# main.net
KiCad netlist of a schematic drawn in EAGLE
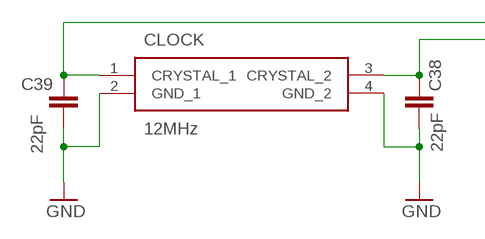
[diagram p0: schematic, sheet 1, part 1 of 3]
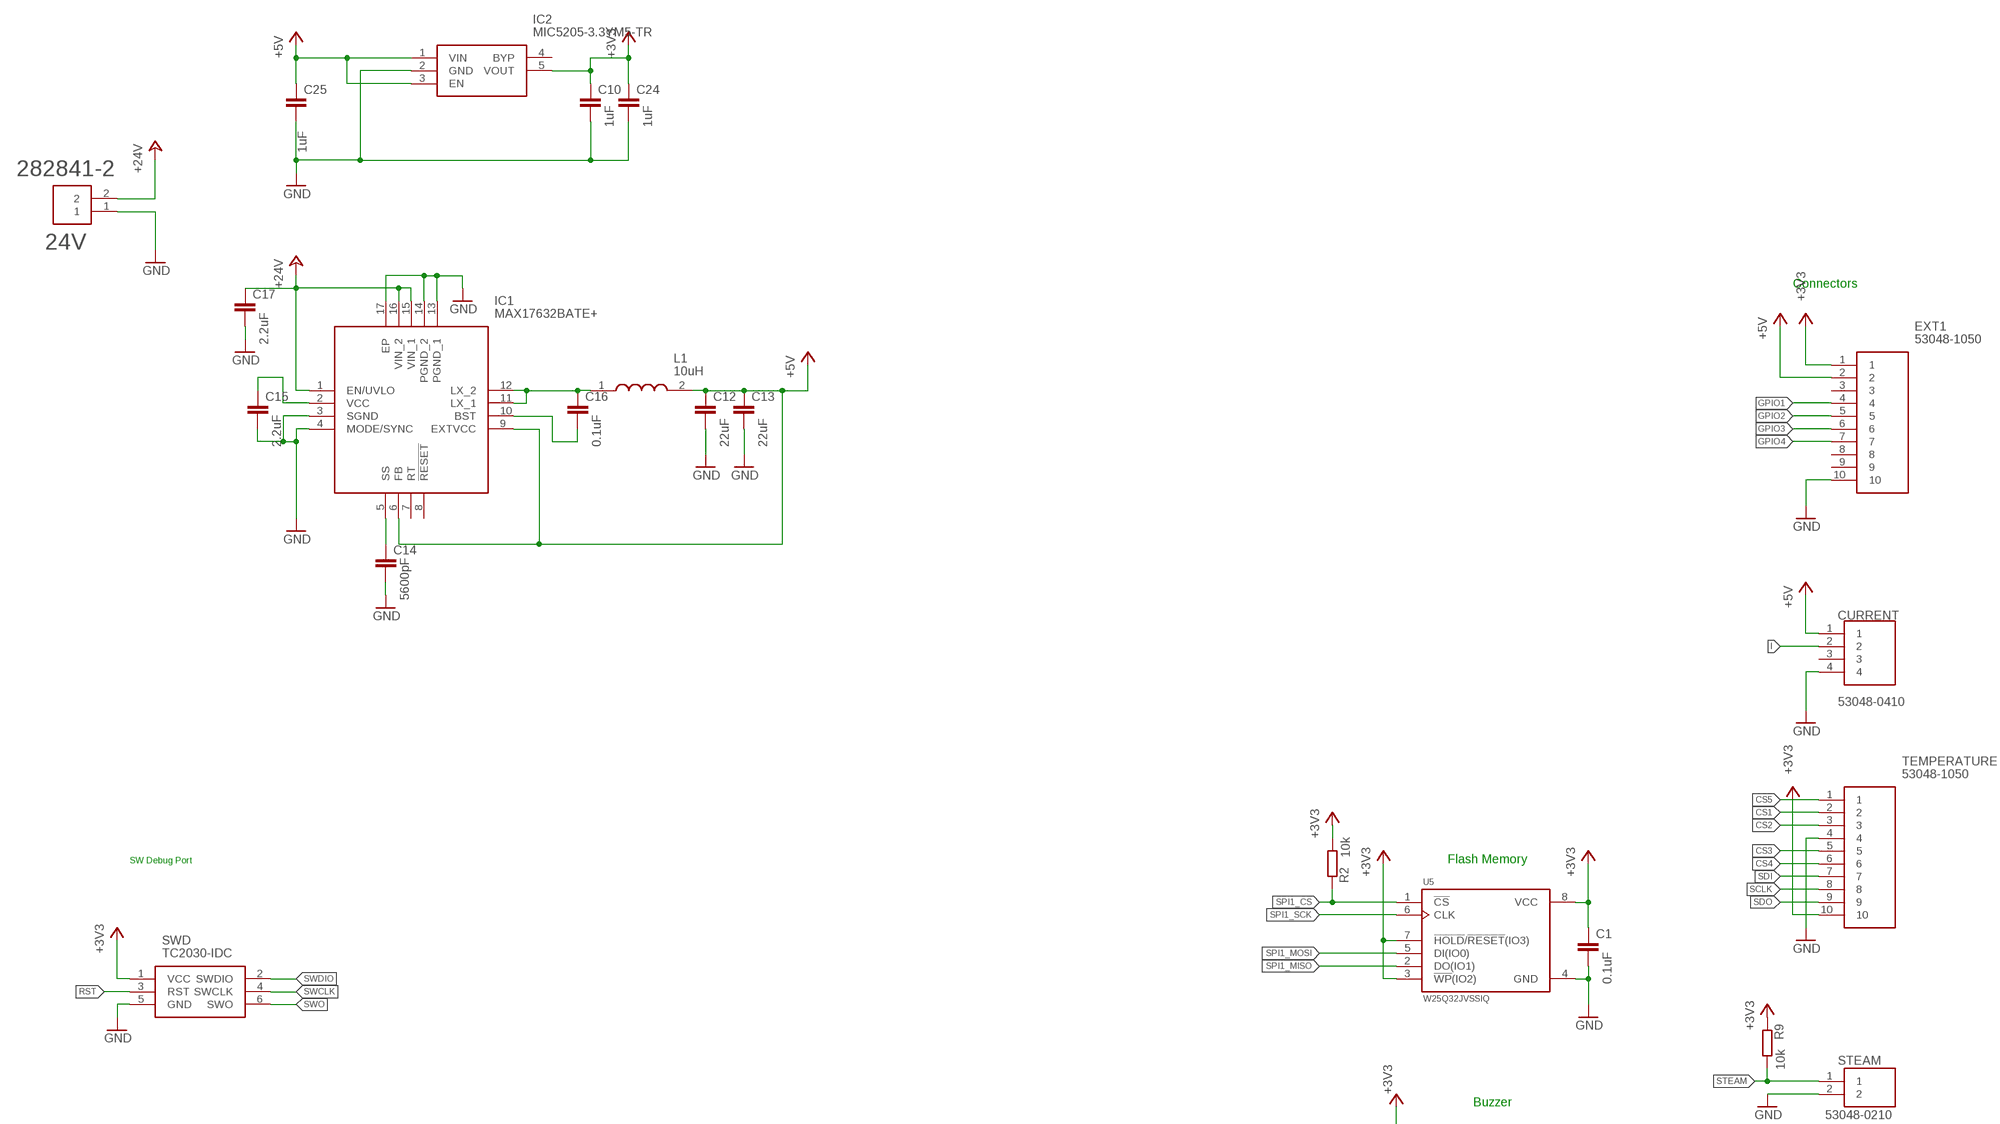
[diagram p1: schematic, sheet 1, part 2 of 3]
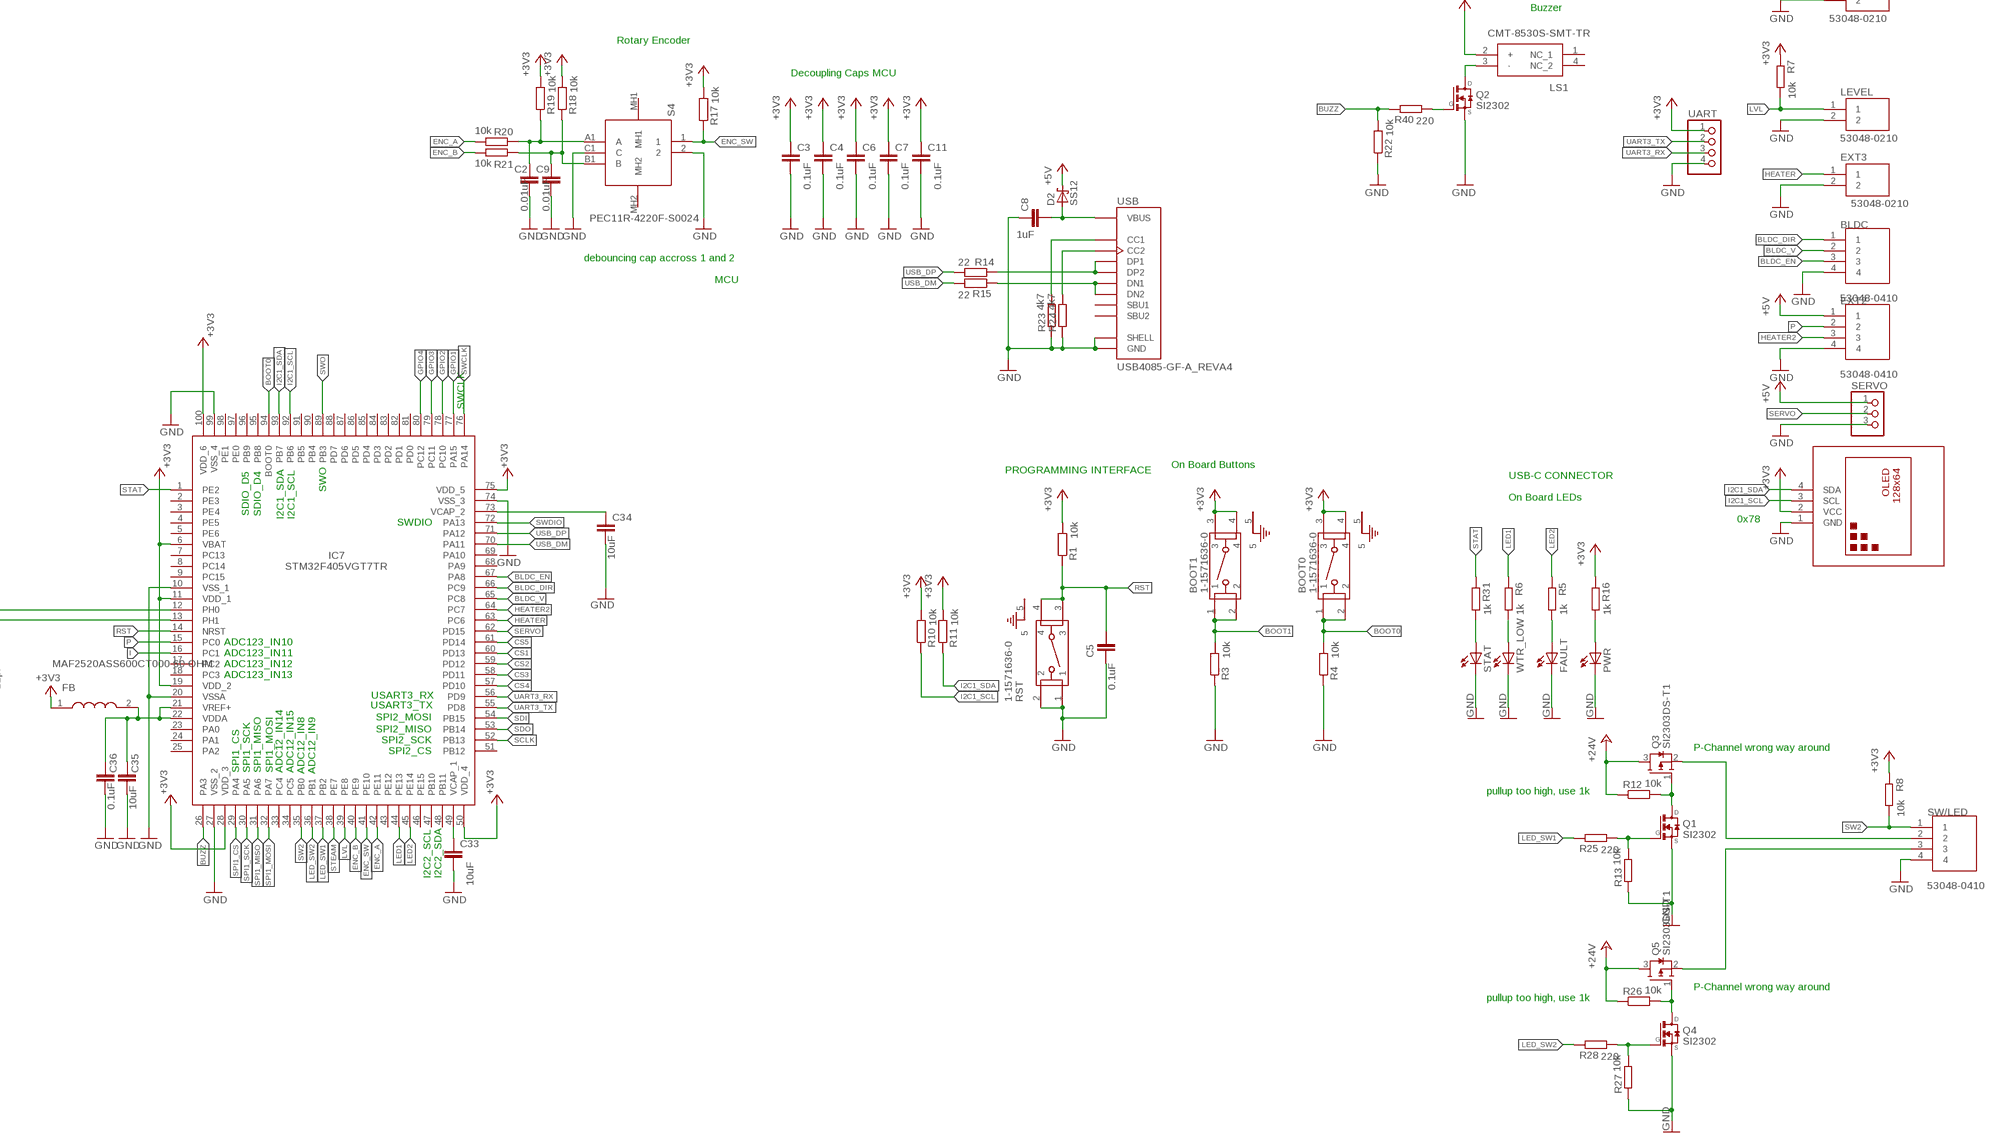
[diagram p2: schematic, sheet 1, part 3 of 3]

(export (version "E")
  (design (tool "Eeschema 10.0.6"))
  (components
    (comp (ref "24V")
      (value "282841-2")
      (footprint "eagle-import:TE_282841-2")
      (fields (field (name "DIGI-KEY_PART_NUMBER") "A98342-ND") (field (name "MF") "TE Connectivity"))
      (libsource (lib "eagle-import") (part "282841-2"))
    )
    (comp (ref "BLDC")
      (value "53048-0410")
      (footprint "eagle-import:530480410")
      (fields (field (name "MOUSER_PART_NUMBER") "538-53048-0410"))
      (libsource (lib "eagle-import") (part "53048-0410"))
    )
    (comp (ref "BOOT0")
      (value "1-1571636-0")
      (footprint "eagle-import:SW5_1571636")
      (fields (field (name "COPYRIGHT") "Copyright (C) 2016 Accelerated Designs. All rights reserved"))
      (libsource (lib "eagle-import") (part "1-1571636-0"))
    )
    (comp (ref "BOOT1")
      (value "1-1571636-0")
      (footprint "eagle-import:SW5_1571636")
      (fields (field (name "COPYRIGHT") "Copyright (C) 2016 Accelerated Designs. All rights reserved"))
      (libsource (lib "eagle-import") (part "1-1571636-0"))
    )
    (comp (ref "C1")
      (value "0.1uF")
      (footprint "eagle-import:C0603K")
      (libsource (lib "eagle-import") (part "C-EUC0603K"))
    )
    (comp (ref "C2")
      (value "0.01uF")
      (footprint "eagle-import:C0603K")
      (libsource (lib "eagle-import") (part "C-EUC0603K"))
    )
    (comp (ref "C3")
      (value "0.1uF")
      (footprint "eagle-import:C0603K")
      (libsource (lib "eagle-import") (part "C-EUC0603K"))
    )
    (comp (ref "C4")
      (value "0.1uF")
      (footprint "eagle-import:C0603K")
      (libsource (lib "eagle-import") (part "C-EUC0603K"))
    )
    (comp (ref "C5")
      (value "0.1uF")
      (footprint "eagle-import:C0603K")
      (libsource (lib "eagle-import") (part "C-EUC0603K"))
    )
    (comp (ref "C6")
      (value "0.1uF")
      (footprint "eagle-import:C0603K")
      (libsource (lib "eagle-import") (part "C-EUC0603K"))
    )
    (comp (ref "C7")
      (value "0.1uF")
      (footprint "eagle-import:C0603K")
      (libsource (lib "eagle-import") (part "C-EUC0603K"))
    )
    (comp (ref "C8")
      (value "1uF")
      (footprint "eagle-import:C0603K")
      (libsource (lib "eagle-import") (part "C-EUC0603K"))
    )
    (comp (ref "C9")
      (value "0.01uF")
      (footprint "eagle-import:C0603K")
      (libsource (lib "eagle-import") (part "C-EUC0603K"))
    )
    (comp (ref "C10")
      (value "1uF")
      (footprint "eagle-import:C0603K")
      (libsource (lib "eagle-import") (part "C-EUC0603K"))
    )
    (comp (ref "C11")
      (value "0.1uF")
      (footprint "eagle-import:C0603K")
      (libsource (lib "eagle-import") (part "C-EUC0603K"))
    )
    (comp (ref "C12")
      (value "22uF")
      (footprint "eagle-import:C0603K")
      (libsource (lib "eagle-import") (part "C-EUC0603K"))
    )
    (comp (ref "C13")
      (value "22uF")
      (footprint "eagle-import:C0603K")
      (libsource (lib "eagle-import") (part "C-EUC0603K"))
    )
    (comp (ref "C14")
      (value "5600pF")
      (footprint "eagle-import:C0603K")
      (libsource (lib "eagle-import") (part "C-EUC0603K"))
    )
    (comp (ref "C15")
      (value "2.2uF")
      (footprint "eagle-import:C0603K")
      (libsource (lib "eagle-import") (part "C-EUC0603K"))
    )
    (comp (ref "C16")
      (value "0.1uF")
      (footprint "eagle-import:C0603K")
      (libsource (lib "eagle-import") (part "C-EUC0603K"))
    )
    (comp (ref "C17")
      (value "2.2uF")
      (footprint "eagle-import:C0603K")
      (libsource (lib "eagle-import") (part "C-EUC0603K"))
    )
    (comp (ref "C24")
      (value "1uF")
      (footprint "eagle-import:C0603K")
      (libsource (lib "eagle-import") (part "C-EUC0603K"))
    )
    (comp (ref "C25")
      (value "1uF")
      (footprint "eagle-import:C0603K")
      (libsource (lib "eagle-import") (part "C-EUC0603K"))
    )
    (comp (ref "C33")
      (value "10uF")
      (footprint "eagle-import:C0603K")
      (libsource (lib "eagle-import") (part "C-EUC0603K"))
    )
    (comp (ref "C34")
      (value "10uF")
      (footprint "eagle-import:C0603K")
      (libsource (lib "eagle-import") (part "C-EUC0603K"))
    )
    (comp (ref "C35")
      (value "10uF")
      (footprint "eagle-import:C0603K")
      (libsource (lib "eagle-import") (part "C-EUC0603K"))
    )
    (comp (ref "C36")
      (value "0.1uF")
      (footprint "eagle-import:C0603K")
      (libsource (lib "eagle-import") (part "C-EUC0603K"))
    )
    (comp (ref "C38")
      (value "22pF")
      (footprint "eagle-import:C0603K")
      (libsource (lib "eagle-import") (part "C-EUC0603K"))
    )
    (comp (ref "C39")
      (value "22pF")
      (footprint "eagle-import:C0603K")
      (libsource (lib "eagle-import") (part "C-EUC0603K"))
    )
    (comp (ref "CLOCK")
      (value "12MHz")
      (footprint "eagle-import:ABM8AIG8000MHZ1ZT")
      (fields
        (field (name "MANUFACTURER_PART_NUMBER") "ABM8AIG-8.000MHZ-1Z-T")
        (field (name "MOUSER_PART_NUMBER") "815-M8AIG-8-1ZT")
      )
      (libsource (lib "eagle-import") (part "ABM8AIG-8.000MHZ-1Z-T"))
    )
    (comp (ref "CURRENT")
      (value "53048-0410")
      (footprint "eagle-import:530480410")
      (fields (field (name "MOUSER_PART_NUMBER") "538-53048-0410"))
      (libsource (lib "eagle-import") (part "53048-0410"))
    )
    (comp (ref "D2")
      (value "SS12")
      (footprint "eagle-import:DO214AC")
      (fields (field (name "MF") "Klein Tools,"))
      (libsource (lib "eagle-import") (part "SS12"))
    )
    (comp (ref "DISPLAY")
      (value "DISPLAY-OLED-128X64-I2C")
      (footprint "eagle-import:DISPLAY-OLED-128X64-I2C")
      (libsource (lib "eagle-import") (part "DISPLAY-OLED-128X64-I2C"))
    )
    (comp (ref "EXT1")
      (value "53048-1050")
      (footprint "eagle-import:SHDRRA10W25P0X125_1X10_1425X55")
      (fields (field (name "MOUSER_PART_NUMBER") "538-53048-1050"))
      (libsource (lib "eagle-import") (part "53048-1050"))
    )
    (comp (ref "EXT2")
      (value "53048-0410")
      (footprint "eagle-import:530480410")
      (fields (field (name "MOUSER_PART_NUMBER") "538-53048-0410"))
      (libsource (lib "eagle-import") (part "53048-0410"))
    )
    (comp (ref "EXT3")
      (value "53048-0210")
      (footprint "eagle-import:SHDRRA2W35P0X125_1X2_425X550X3")
      (fields (field (name "MOUSER_PART_NUMBER") "538-53048-0210"))
      (libsource (lib "eagle-import") (part "53048-0210"))
    )
    (comp (ref "FAULT")
      (value "LEDCHIPLED_0805")
      (footprint "eagle-import:CHIPLED_0805")
      (libsource (lib "eagle-import") (part "LEDCHIPLED_0805"))
    )
    (comp (ref "FB")
      (value "MAF2520ASS600CT000 60 OHM")
      (footprint "eagle-import:INDC2520X120N")
      (fields
        (field (name "MANUFACTURER_PART_NUMBER") "DFE252012P-1R0M=P2")
        (field (name "MOUSER_PART_NUMBER") "81-DFE252012P-1R0MP2")
        (field (name "RS_PART_NUMBER") "1058572P")
      )
      (libsource (lib "eagle-import") (part "DFE252012P-1R0M=P2"))
    )
    (comp (ref "IC1")
      (value "MAX17632BATE+")
      (footprint "eagle-import:QFN50P300X300X80-17N")
      (fields (field (name "MOUSER_PART_NUMBER") "700-MAX17632BATE+"))
      (libsource (lib "eagle-import") (part "MAX17632BATE+"))
    )
    (comp (ref "IC2")
      (value "MIC5205-3.3YM5-TR")
      (footprint "eagle-import:SOT95P280X145-5N")
      (fields (field (name "MOUSER_PART_NUMBER") "998-MIC5205-3.3YM5TR"))
      (libsource (lib "eagle-import") (part "MIC5205-3.3YM5-TR"))
    )
    (comp (ref "IC7")
      (value "STM32F405VGT7TR")
      (footprint "eagle-import:QFP50P1600X1600X160-100N")
      (fields
        (field (name "MOUSER_PART_NUMBER") "511-STM32F405VGT7TR")
        (field (name "RS_PART_NUMBER") "7926025")
      )
      (libsource (lib "eagle-import") (part "STM32F405VGT7TR"))
    )
    (comp (ref "L1")
      (value "10uH")
      (footprint "eagle-import:INDC3225X270N")
      (fields
        (field (name "ARROW_PART_NUMBER") "CBC3225T100KR")
        (field (name "MOUSER_PART_NUMBER") "963-CBC3225T100KR")
      )
      (libsource (lib "eagle-import") (part "CBC3225T100KR"))
    )
    (comp (ref "LEVEL")
      (value "53048-0210")
      (footprint "eagle-import:SHDRRA2W35P0X125_1X2_425X550X3")
      (fields (field (name "MOUSER_PART_NUMBER") "538-53048-0210"))
      (libsource (lib "eagle-import") (part "53048-0210"))
    )
    (comp (ref "LS1")
      (value "CMT-8530S-SMT-TR")
      (footprint "eagle-import:CMT8530SSMTTR")
      (fields (field (name "MOUSER_PART_NUMBER") "490-CMT-8530S-SMT-TR"))
      (libsource (lib "eagle-import") (part "CMT-8530S-SMT-TR"))
    )
    (comp (ref "PWR")
      (value "LEDCHIPLED_0805")
      (footprint "eagle-import:CHIPLED_0805")
      (libsource (lib "eagle-import") (part "LEDCHIPLED_0805"))
    )
    (comp (ref "Q1")
      (value "SI2302")
      (footprint "eagle-import:SOT23")
      (fields (field (name "MF") "Micro Commercial Components _MCC_"))
      (libsource (lib "eagle-import") (part "SI2302"))
    )
    (comp (ref "Q2")
      (value "SI2302")
      (footprint "eagle-import:SOT23")
      (fields (field (name "MF") "Micro Commercial Components _MCC_"))
      (libsource (lib "eagle-import") (part "SI2302"))
    )
    (comp (ref "Q3")
      (value "SI2303DS-T1")
      (footprint "eagle-import:SOT90P248X115-3N")
      (fields (field (name "MOUSER_PART_NUMBER") "781-SI2303DS"))
      (libsource (lib "eagle-import") (part "SI2303DS-T1"))
    )
    (comp (ref "Q4")
      (value "SI2302")
      (footprint "eagle-import:SOT23")
      (fields (field (name "MF") "Micro Commercial Components _MCC_"))
      (libsource (lib "eagle-import") (part "SI2302"))
    )
    (comp (ref "Q5")
      (value "SI2303DS-T1")
      (footprint "eagle-import:SOT90P248X115-3N")
      (fields (field (name "MOUSER_PART_NUMBER") "781-SI2303DS"))
      (libsource (lib "eagle-import") (part "SI2303DS-T1"))
    )
    (comp (ref "R1")
      (value "10k")
      (footprint "eagle-import:R0603")
      (libsource (lib "eagle-import") (part "R-EU_R0603"))
    )
    (comp (ref "R2")
      (value "10k")
      (footprint "eagle-import:R0603")
      (libsource (lib "eagle-import") (part "R-EU_R0603"))
    )
    (comp (ref "R3")
      (value "10k")
      (footprint "eagle-import:R0603")
      (libsource (lib "eagle-import") (part "R-EU_R0603"))
    )
    (comp (ref "R4")
      (value "10k")
      (footprint "eagle-import:R0603")
      (libsource (lib "eagle-import") (part "R-EU_R0603"))
    )
    (comp (ref "R5")
      (value "1k")
      (footprint "eagle-import:R0603")
      (libsource (lib "eagle-import") (part "R-EU_R0603"))
    )
    (comp (ref "R6")
      (value "1k")
      (footprint "eagle-import:R0603")
      (libsource (lib "eagle-import") (part "R-EU_R0603"))
    )
    (comp (ref "R7")
      (value "10k")
      (footprint "eagle-import:R0603")
      (libsource (lib "eagle-import") (part "R-EU_R0603"))
    )
    (comp (ref "R8")
      (value "10k")
      (footprint "eagle-import:R0603")
      (libsource (lib "eagle-import") (part "R-EU_R0603"))
    )
    (comp (ref "R9")
      (value "10k")
      (footprint "eagle-import:R0603")
      (libsource (lib "eagle-import") (part "R-EU_R0603"))
    )
    (comp (ref "R10")
      (value "10k")
      (footprint "eagle-import:R0603")
      (libsource (lib "eagle-import") (part "R-EU_R0603"))
    )
    (comp (ref "R11")
      (value "10k")
      (footprint "eagle-import:R0603")
      (libsource (lib "eagle-import") (part "R-EU_R0603"))
    )
    (comp (ref "R12")
      (value "10k")
      (footprint "eagle-import:R0603")
      (libsource (lib "eagle-import") (part "R-EU_R0603"))
    )
    (comp (ref "R13")
      (value "10k")
      (footprint "eagle-import:R0603")
      (libsource (lib "eagle-import") (part "R-EU_R0603"))
    )
    (comp (ref "R14")
      (value "22")
      (footprint "eagle-import:R0603")
      (libsource (lib "eagle-import") (part "R-EU_R0603"))
    )
    (comp (ref "R15")
      (value "22")
      (footprint "eagle-import:R0603")
      (libsource (lib "eagle-import") (part "R-EU_R0603"))
    )
    (comp (ref "R16")
      (value "1k")
      (footprint "eagle-import:R0603")
      (libsource (lib "eagle-import") (part "R-EU_R0603"))
    )
    (comp (ref "R17")
      (value "10k")
      (footprint "eagle-import:R0603")
      (libsource (lib "eagle-import") (part "R-EU_R0603"))
    )
    (comp (ref "R18")
      (value "10k")
      (footprint "eagle-import:R0603")
      (libsource (lib "eagle-import") (part "R-EU_R0603"))
    )
    (comp (ref "R19")
      (value "10k")
      (footprint "eagle-import:R0603")
      (libsource (lib "eagle-import") (part "R-EU_R0603"))
    )
    (comp (ref "R20")
      (value "10k")
      (footprint "eagle-import:R0603")
      (libsource (lib "eagle-import") (part "R-EU_R0603"))
    )
    (comp (ref "R21")
      (value "10k")
      (footprint "eagle-import:R0603")
      (libsource (lib "eagle-import") (part "R-EU_R0603"))
    )
    (comp (ref "R22")
      (value "10k")
      (footprint "eagle-import:R0603")
      (libsource (lib "eagle-import") (part "R-EU_R0603"))
    )
    (comp (ref "R23")
      (value "4k7")
      (footprint "eagle-import:R0603")
      (libsource (lib "eagle-import") (part "R-EU_R0603"))
    )
    (comp (ref "R24")
      (value "4k7")
      (footprint "eagle-import:R0603")
      (libsource (lib "eagle-import") (part "R-EU_R0603"))
    )
    (comp (ref "R25")
      (value "220")
      (footprint "eagle-import:R0603")
      (libsource (lib "eagle-import") (part "R-EU_R0603"))
    )
    (comp (ref "R26")
      (value "10k")
      (footprint "eagle-import:R0603")
      (libsource (lib "eagle-import") (part "R-EU_R0603"))
    )
    (comp (ref "R27")
      (value "10k")
      (footprint "eagle-import:R0603")
      (libsource (lib "eagle-import") (part "R-EU_R0603"))
    )
    (comp (ref "R28")
      (value "220")
      (footprint "eagle-import:R0603")
      (libsource (lib "eagle-import") (part "R-EU_R0603"))
    )
    (comp (ref "R31")
      (value "1k")
      (footprint "eagle-import:R0603")
      (libsource (lib "eagle-import") (part "R-EU_R0603"))
    )
    (comp (ref "R40")
      (value "220")
      (footprint "eagle-import:R0603")
      (libsource (lib "eagle-import") (part "R-EU_R0603"))
    )
    (comp (ref "RST")
      (value "1-1571636-0")
      (footprint "eagle-import:SW5_1571636")
      (fields (field (name "COPYRIGHT") "Copyright (C) 2016 Accelerated Designs. All rights reserved"))
      (libsource (lib "eagle-import") (part "1-1571636-0"))
    )
    (comp (ref "S4")
      (value "PEC11R-4220F-S0024")
      (footprint "eagle-import:PEC11R4220FS0024")
      (fields (field (name "MOUSER_PART_NUMBER") "652-PEC11R-4220F-S24"))
      (libsource (lib "eagle-import") (part "PEC11R-4220F-S0024"))
    )
    (comp (ref "SERVO")
      (value "PINHD-1X3/90")
      (footprint "eagle-import:1X03_90")
      (libsource (lib "eagle-import") (part "PINHD-1X3/90"))
    )
    (comp (ref "STAT")
      (value "LEDCHIPLED_0805")
      (footprint "eagle-import:CHIPLED_0805")
      (libsource (lib "eagle-import") (part "LEDCHIPLED_0805"))
    )
    (comp (ref "STEAM")
      (value "53048-0210")
      (footprint "eagle-import:SHDRRA2W35P0X125_1X2_425X550X3")
      (fields (field (name "MOUSER_PART_NUMBER") "538-53048-0210"))
      (libsource (lib "eagle-import") (part "53048-0210"))
    )
    (comp (ref "SW/LED")
      (value "53048-0410")
      (footprint "eagle-import:530480410")
      (fields (field (name "MOUSER_PART_NUMBER") "538-53048-0410"))
      (libsource (lib "eagle-import") (part "53048-0410"))
    )
    (comp (ref "SWD")
      (value "TC2030-IDC")
      (footprint "eagle-import:TC2030IDC")
      (libsource (lib "eagle-import") (part "TC2030-IDC"))
    )
    (comp (ref "TEMPERATURE")
      (value "53048-1050")
      (footprint "eagle-import:SHDRRA10W25P0X125_1X10_1425X55")
      (fields (field (name "MOUSER_PART_NUMBER") "538-53048-1050"))
      (libsource (lib "eagle-import") (part "53048-1050"))
    )
    (comp (ref "U5")
      (value "W25Q32JVSSIQ")
      (footprint "eagle-import:SOIC127P790X216-8N")
      (fields (field (name "MF") "Winbond"))
      (libsource (lib "eagle-import") (part "W25Q32JVSSIQ"))
    )
    (comp (ref "UART")
      (value "PINHD-1X4")
      (footprint "eagle-import:1X04")
      (libsource (lib "eagle-import") (part "PINHD-1X4"))
    )
    (comp (ref "USB")
      (value "USB4085-GF-A_REVA4")
      (footprint "eagle-import:GCT_USB4085-GF-A_REVA4")
      (fields (field (name "MF") "Global Connector Technology") (field (name "MP") "USB4085-GF-A"))
      (libsource (lib "eagle-import") (part "USB4085-GF-A_REVA4"))
    )
    (comp (ref "WTR_LOW")
      (value "LEDCHIPLED_0805")
      (footprint "eagle-import:CHIPLED_0805")
      (libsource (lib "eagle-import") (part "LEDCHIPLED_0805"))
    )
  )
  (nets
    (net (code "1") (name "+3V3") (class "Default")
      (node (ref "BOOT0") (pin "3") (pinfunction "3_3") (pintype "passive"))
      (node (ref "BOOT0") (pin "4") (pinfunction "4_4") (pintype "passive"))
      (node (ref "BOOT1") (pin "3") (pinfunction "3_3") (pintype "passive"))
      (node (ref "BOOT1") (pin "4") (pinfunction "4_4") (pintype "passive"))
      (node (ref "C1") (pin "1") (pinfunction "1_1") (pintype "passive"))
      (node (ref "C10") (pin "1") (pinfunction "1_1") (pintype "passive"))
      (node (ref "C11") (pin "1") (pinfunction "1_1") (pintype "passive"))
      (node (ref "C24") (pin "1") (pinfunction "1_1") (pintype "passive"))
      (node (ref "C3") (pin "1") (pinfunction "1_1") (pintype "passive"))
      (node (ref "C4") (pin "1") (pinfunction "1_1") (pintype "passive"))
      (node (ref "C6") (pin "1") (pinfunction "1_1") (pintype "passive"))
      (node (ref "C7") (pin "1") (pinfunction "1_1") (pintype "passive"))
      (node (ref "DISPLAY") (pin "2") (pinfunction "VCC_2") (pintype "power_in"))
      (node (ref "EXT1") (pin "1") (pinfunction "1_1") (pintype "bidirectional"))
      (node (ref "FB") (pin "1") (pinfunction "1_1") (pintype "bidirectional"))
      (node (ref "IC2") (pin "5") (pinfunction "VOUT_5") (pintype "power_in"))
      (node (ref "IC7") (pin "100") (pinfunction "VDD_6_100") (pintype "power_in"))
      (node (ref "IC7") (pin "11") (pinfunction "VDD_1_11") (pintype "power_in"))
      (node (ref "IC7") (pin "19") (pinfunction "VDD_2_19") (pintype "power_in"))
      (node (ref "IC7") (pin "28") (pinfunction "VDD_3_28") (pintype "power_in"))
      (node (ref "IC7") (pin "50") (pinfunction "VDD_4_50") (pintype "power_in"))
      (node (ref "IC7") (pin "6") (pinfunction "VBAT_6") (pintype "bidirectional"))
      (node (ref "IC7") (pin "75") (pinfunction "VDD_5_75") (pintype "power_in"))
      (node (ref "LS1") (pin "2") (pinfunction "+_2") (pintype "bidirectional"))
      (node (ref "R1") (pin "2") (pinfunction "2_2") (pintype "passive"))
      (node (ref "R10") (pin "2") (pinfunction "2_2") (pintype "passive"))
      (node (ref "R11") (pin "2") (pinfunction "2_2") (pintype "passive"))
      (node (ref "R16") (pin "1") (pinfunction "1_1") (pintype "passive"))
      (node (ref "R17") (pin "2") (pinfunction "2_2") (pintype "passive"))
      (node (ref "R18") (pin "2") (pinfunction "2_2") (pintype "passive"))
      (node (ref "R19") (pin "2") (pinfunction "2_2") (pintype "passive"))
      (node (ref "R2") (pin "2") (pinfunction "2_2") (pintype "passive"))
      (node (ref "R7") (pin "1") (pinfunction "1_1") (pintype "passive"))
      (node (ref "R8") (pin "1") (pinfunction "1_1") (pintype "passive"))
      (node (ref "R9") (pin "1") (pinfunction "1_1") (pintype "passive"))
      (node (ref "SWD") (pin "1") (pinfunction "VCC_1") (pintype "bidirectional"))
      (node (ref "TEMPERATURE") (pin "10") (pinfunction "10_10") (pintype "bidirectional"))
      (node (ref "U5") (pin "3") (pinfunction "~{WP}(IO2)_3") (pintype "bidirectional"))
      (node (ref "U5") (pin "7") (pinfunction "~{HOLD}/~{RESET}(IO3)_7") (pintype "bidirectional"))
      (node (ref "U5") (pin "8") (pinfunction "VCC_8") (pintype "power_in"))
      (node (ref "UART") (pin "1") (pinfunction "1_1") (pintype "passive"))
    )
    (net (code "2") (name "+5V") (class "Default")
      (node (ref "C12") (pin "1") (pinfunction "1_1") (pintype "passive"))
      (node (ref "C13") (pin "1") (pinfunction "1_1") (pintype "passive"))
      (node (ref "C25") (pin "1") (pinfunction "1_1") (pintype "passive"))
      (node (ref "CURRENT") (pin "1") (pinfunction "1_1") (pintype "bidirectional"))
      (node (ref "D2") (pin "C") (pinfunction "C_C") (pintype "passive"))
      (node (ref "EXT1") (pin "2") (pinfunction "2_2") (pintype "bidirectional"))
      (node (ref "EXT2") (pin "1") (pinfunction "1_1") (pintype "bidirectional"))
      (node (ref "IC1") (pin "6") (pinfunction "FB_6") (pintype "bidirectional"))
      (node (ref "IC1") (pin "9") (pinfunction "EXTVCC_9") (pintype "bidirectional"))
      (node (ref "IC2") (pin "1") (pinfunction "VIN_1") (pintype "power_in"))
      (node (ref "IC2") (pin "3") (pinfunction "EN_3") (pintype "input"))
      (node (ref "L1") (pin "2") (pinfunction "2_2") (pintype "bidirectional"))
      (node (ref "SERVO") (pin "1") (pinfunction "1_1") (pintype "passive"))
    )
    (net (code "3") (name "+24V") (class "Default")
      (node (ref "24V") (pin "2") (pinfunction "2_2") (pintype "passive"))
      (node (ref "C17") (pin "1") (pinfunction "1_1") (pintype "passive"))
      (node (ref "IC1") (pin "1") (pinfunction "EN/UVLO_1") (pintype "bidirectional"))
      (node (ref "IC1") (pin "15") (pinfunction "VIN_1_15") (pintype "bidirectional"))
      (node (ref "IC1") (pin "16") (pinfunction "VIN_2_16") (pintype "bidirectional"))
      (node (ref "Q3") (pin "3") (pinfunction "D_3") (pintype "bidirectional"))
      (node (ref "Q5") (pin "3") (pinfunction "D_3") (pintype "bidirectional"))
      (node (ref "R12") (pin "1") (pinfunction "1_1") (pintype "passive"))
      (node (ref "R26") (pin "1") (pinfunction "1_1") (pintype "passive"))
    )
    (net (code "4") (name "BLDC_DIR") (class "Default")
      (node (ref "BLDC") (pin "1") (pinfunction "1_1") (pintype "bidirectional"))
      (node (ref "IC7") (pin "66") (pinfunction "PC9_66") (pintype "bidirectional"))
    )
    (net (code "5") (name "BLDC_EN") (class "Default")
      (node (ref "BLDC") (pin "3") (pinfunction "3_3") (pintype "bidirectional"))
      (node (ref "IC7") (pin "67") (pinfunction "PA8_67") (pintype "bidirectional"))
    )
    (net (code "6") (name "BLDC_V") (class "Default")
      (node (ref "BLDC") (pin "2") (pinfunction "2_2") (pintype "bidirectional"))
      (node (ref "IC7") (pin "65") (pinfunction "PC8_65") (pintype "bidirectional"))
    )
    (net (code "7") (name "BOOT0") (class "Default")
      (node (ref "BOOT0") (pin "1") (pinfunction "1_1") (pintype "passive"))
      (node (ref "BOOT0") (pin "2") (pinfunction "2_2") (pintype "passive"))
      (node (ref "IC7") (pin "94") (pinfunction "BOOT0_94") (pintype "bidirectional"))
      (node (ref "R4") (pin "2") (pinfunction "2_2") (pintype "passive"))
    )
    (net (code "8") (name "BOOT1") (class "Default")
      (node (ref "BOOT1") (pin "1") (pinfunction "1_1") (pintype "passive"))
      (node (ref "BOOT1") (pin "2") (pinfunction "2_2") (pintype "passive"))
      (node (ref "R3") (pin "2") (pinfunction "2_2") (pintype "passive"))
    )
    (net (code "9") (name "BUZZ") (class "Default")
      (node (ref "IC7") (pin "26") (pinfunction "PA3_26") (pintype "bidirectional"))
      (node (ref "R22") (pin "2") (pinfunction "2_2") (pintype "passive"))
      (node (ref "R40") (pin "1") (pinfunction "1_1") (pintype "passive"))
    )
    (net (code "10") (name "CS1") (class "Default")
      (node (ref "IC7") (pin "60") (pinfunction "PD13_60") (pintype "bidirectional"))
      (node (ref "TEMPERATURE") (pin "2") (pinfunction "2_2") (pintype "bidirectional"))
    )
    (net (code "11") (name "CS2") (class "Default")
      (node (ref "IC7") (pin "59") (pinfunction "PD12_59") (pintype "bidirectional"))
      (node (ref "TEMPERATURE") (pin "3") (pinfunction "3_3") (pintype "bidirectional"))
    )
    (net (code "12") (name "CS3") (class "Default")
      (node (ref "IC7") (pin "58") (pinfunction "PD11_58") (pintype "bidirectional"))
      (node (ref "TEMPERATURE") (pin "5") (pinfunction "5_5") (pintype "bidirectional"))
    )
    (net (code "13") (name "CS4") (class "Default")
      (node (ref "IC7") (pin "57") (pinfunction "PD10_57") (pintype "bidirectional"))
      (node (ref "TEMPERATURE") (pin "6") (pinfunction "6_6") (pintype "bidirectional"))
    )
    (net (code "14") (name "CS5") (class "Default")
      (node (ref "IC7") (pin "61") (pinfunction "PD14_61") (pintype "bidirectional"))
      (node (ref "TEMPERATURE") (pin "1") (pinfunction "1_1") (pintype "bidirectional"))
    )
    (net (code "15") (name "ENC_A") (class "Default")
      (node (ref "IC7") (pin "42") (pinfunction "PE11_42") (pintype "bidirectional"))
      (node (ref "R20") (pin "2") (pinfunction "2_2") (pintype "passive"))
    )
    (net (code "16") (name "ENC_B") (class "Default")
      (node (ref "IC7") (pin "40") (pinfunction "PE9_40") (pintype "bidirectional"))
      (node (ref "R21") (pin "2") (pinfunction "2_2") (pintype "passive"))
    )
    (net (code "17") (name "ENC_SW") (class "Default")
      (node (ref "IC7") (pin "41") (pinfunction "PE10_41") (pintype "bidirectional"))
      (node (ref "R17") (pin "1") (pinfunction "1_1") (pintype "passive"))
      (node (ref "S4") (pin "1") (pinfunction "1_1") (pintype "bidirectional"))
    )
    (net (code "18") (name "GND") (class "Default")
      (node (ref "24V") (pin "1") (pinfunction "1_1") (pintype "passive"))
      (node (ref "BLDC") (pin "4") (pinfunction "4_4") (pintype "bidirectional"))
      (node (ref "C1") (pin "2") (pinfunction "2_2") (pintype "passive"))
      (node (ref "C10") (pin "2") (pinfunction "2_2") (pintype "passive"))
      (node (ref "C11") (pin "2") (pinfunction "2_2") (pintype "passive"))
      (node (ref "C12") (pin "2") (pinfunction "2_2") (pintype "passive"))
      (node (ref "C13") (pin "2") (pinfunction "2_2") (pintype "passive"))
      (node (ref "C14") (pin "2") (pinfunction "2_2") (pintype "passive"))
      (node (ref "C15") (pin "2") (pinfunction "2_2") (pintype "passive"))
      (node (ref "C17") (pin "2") (pinfunction "2_2") (pintype "passive"))
      (node (ref "C2") (pin "2") (pinfunction "2_2") (pintype "passive"))
      (node (ref "C24") (pin "2") (pinfunction "2_2") (pintype "passive"))
      (node (ref "C25") (pin "2") (pinfunction "2_2") (pintype "passive"))
      (node (ref "C3") (pin "2") (pinfunction "2_2") (pintype "passive"))
      (node (ref "C33") (pin "2") (pinfunction "2_2") (pintype "passive"))
      (node (ref "C34") (pin "2") (pinfunction "2_2") (pintype "passive"))
      (node (ref "C35") (pin "2") (pinfunction "2_2") (pintype "passive"))
      (node (ref "C36") (pin "2") (pinfunction "2_2") (pintype "passive"))
      (node (ref "C38") (pin "2") (pinfunction "2_2") (pintype "passive"))
      (node (ref "C39") (pin "2") (pinfunction "2_2") (pintype "passive"))
      (node (ref "C4") (pin "2") (pinfunction "2_2") (pintype "passive"))
      (node (ref "C5") (pin "2") (pinfunction "2_2") (pintype "passive"))
      (node (ref "C6") (pin "2") (pinfunction "2_2") (pintype "passive"))
      (node (ref "C7") (pin "2") (pinfunction "2_2") (pintype "passive"))
      (node (ref "C8") (pin "1") (pinfunction "1_1") (pintype "passive"))
      (node (ref "C9") (pin "2") (pinfunction "2_2") (pintype "passive"))
      (node (ref "CLOCK") (pin "2") (pinfunction "GND_1_2") (pintype "bidirectional"))
      (node (ref "CLOCK") (pin "4") (pinfunction "GND_2_4") (pintype "bidirectional"))
      (node (ref "CURRENT") (pin "4") (pinfunction "4_4") (pintype "bidirectional"))
      (node (ref "DISPLAY") (pin "1") (pinfunction "GND_1") (pintype "power_in"))
      (node (ref "EXT1") (pin "10") (pinfunction "10_10") (pintype "bidirectional"))
      (node (ref "EXT2") (pin "4") (pinfunction "4_4") (pintype "bidirectional"))
      (node (ref "EXT3") (pin "2") (pinfunction "2_2") (pintype "bidirectional"))
      (node (ref "FAULT") (pin "C") (pinfunction "C_C") (pintype "passive"))
      (node (ref "IC1") (pin "13") (pinfunction "PGND_1_13") (pintype "bidirectional"))
      (node (ref "IC1") (pin "14") (pinfunction "PGND_2_14") (pintype "bidirectional"))
      (node (ref "IC1") (pin "17") (pinfunction "EP_17") (pintype "bidirectional"))
      (node (ref "IC1") (pin "3") (pinfunction "SGND_3") (pintype "bidirectional"))
      (node (ref "IC1") (pin "4") (pinfunction "MODE/SYNC_4") (pintype "bidirectional"))
      (node (ref "IC2") (pin "2") (pinfunction "GND_2") (pintype "power_in"))
      (node (ref "IC7") (pin "10") (pinfunction "VSS_1_10") (pintype "power_in"))
      (node (ref "IC7") (pin "20") (pinfunction "VSSA_20") (pintype "power_in"))
      (node (ref "IC7") (pin "27") (pinfunction "VSS_2_27") (pintype "power_in"))
      (node (ref "IC7") (pin "74") (pinfunction "VSS_3_74") (pintype "power_in"))
      (node (ref "IC7") (pin "99") (pinfunction "VSS_4_99") (pintype "power_in"))
      (node (ref "LEVEL") (pin "2") (pinfunction "2_2") (pintype "bidirectional"))
      (node (ref "PWR") (pin "C") (pinfunction "C_C") (pintype "passive"))
      (node (ref "Q1") (pin "2") (pinfunction "S_2") (pintype "passive"))
      (node (ref "Q2") (pin "2") (pinfunction "S_2") (pintype "passive"))
      (node (ref "Q4") (pin "2") (pinfunction "S_2") (pintype "passive"))
      (node (ref "R13") (pin "1") (pinfunction "1_1") (pintype "passive"))
      (node (ref "R22") (pin "1") (pinfunction "1_1") (pintype "passive"))
      (node (ref "R23") (pin "1") (pinfunction "1_1") (pintype "passive"))
      (node (ref "R24") (pin "1") (pinfunction "1_1") (pintype "passive"))
      (node (ref "R27") (pin "1") (pinfunction "1_1") (pintype "passive"))
      (node (ref "R3") (pin "1") (pinfunction "1_1") (pintype "passive"))
      (node (ref "R4") (pin "1") (pinfunction "1_1") (pintype "passive"))
      (node (ref "RST") (pin "1") (pinfunction "1_1") (pintype "passive"))
      (node (ref "RST") (pin "2") (pinfunction "2_2") (pintype "passive"))
      (node (ref "S4") (pin "2") (pinfunction "2_2") (pintype "bidirectional"))
      (node (ref "S4") (pin "C1") (pinfunction "C_C1") (pintype "bidirectional"))
      (node (ref "SERVO") (pin "3") (pinfunction "3_3") (pintype "passive"))
      (node (ref "STAT") (pin "C") (pinfunction "C_C") (pintype "passive"))
      (node (ref "STEAM") (pin "2") (pinfunction "2_2") (pintype "bidirectional"))
      (node (ref "SW/LED") (pin "4") (pinfunction "4_4") (pintype "bidirectional"))
      (node (ref "SWD") (pin "5") (pinfunction "GND_5") (pintype "bidirectional"))
      (node (ref "TEMPERATURE") (pin "4") (pinfunction "4_4") (pintype "bidirectional"))
      (node (ref "U5") (pin "4") (pinfunction "GND_4") (pintype "power_in"))
      (node (ref "UART") (pin "4") (pinfunction "4_4") (pintype "passive"))
      (node (ref "USB") (pin "A1") (pinfunction "GND_A1") (pintype "passive"))
      (node (ref "USB") (pin "A12") (pinfunction "GND_A12") (pintype "passive"))
      (node (ref "USB") (pin "B1") (pinfunction "GND_B1") (pintype "passive"))
      (node (ref "USB") (pin "B12") (pinfunction "GND_B12") (pintype "passive"))
      (node (ref "USB") (pin "P1") (pinfunction "SHELL_P1") (pintype "passive"))
      (node (ref "USB") (pin "P2") (pinfunction "SHELL_P2") (pintype "passive"))
      (node (ref "USB") (pin "P3") (pinfunction "SHELL_P3") (pintype "passive"))
      (node (ref "USB") (pin "P4") (pinfunction "SHELL_P4") (pintype "passive"))
      (node (ref "WTR_LOW") (pin "C") (pinfunction "C_C") (pintype "passive"))
    )
    (net (code "19") (name "GPIO1") (class "Default")
      (node (ref "EXT1") (pin "4") (pinfunction "4_4") (pintype "bidirectional"))
      (node (ref "IC7") (pin "77") (pinfunction "PA15_77") (pintype "bidirectional"))
    )
    (net (code "20") (name "GPIO2") (class "Default")
      (node (ref "EXT1") (pin "5") (pinfunction "5_5") (pintype "bidirectional"))
      (node (ref "IC7") (pin "78") (pinfunction "PC10_78") (pintype "bidirectional"))
    )
    (net (code "21") (name "GPIO3") (class "Default")
      (node (ref "EXT1") (pin "6") (pinfunction "6_6") (pintype "bidirectional"))
      (node (ref "IC7") (pin "79") (pinfunction "PC11_79") (pintype "bidirectional"))
    )
    (net (code "22") (name "GPIO4") (class "Default")
      (node (ref "EXT1") (pin "7") (pinfunction "7_7") (pintype "bidirectional"))
      (node (ref "IC7") (pin "80") (pinfunction "PC12_80") (pintype "bidirectional"))
    )
    (net (code "23") (name "HEATER") (class "Default")
      (node (ref "EXT3") (pin "1") (pinfunction "1_1") (pintype "bidirectional"))
      (node (ref "IC7") (pin "63") (pinfunction "PC6_63") (pintype "bidirectional"))
    )
    (net (code "24") (name "HEATER2") (class "Default")
      (node (ref "EXT2") (pin "3") (pinfunction "3_3") (pintype "bidirectional"))
      (node (ref "IC7") (pin "64") (pinfunction "PC7_64") (pintype "bidirectional"))
    )
    (net (code "25") (name "I") (class "Default")
      (node (ref "CURRENT") (pin "2") (pinfunction "2_2") (pintype "bidirectional"))
      (node (ref "IC7") (pin "16") (pinfunction "PC1_16") (pintype "bidirectional"))
    )
    (net (code "26") (name "I2C1_SCL") (class "Default")
      (node (ref "DISPLAY") (pin "3") (pinfunction "SCL_3") (pintype "bidirectional"))
      (node (ref "IC7") (pin "92") (pinfunction "PB6_92") (pintype "bidirectional"))
      (node (ref "R10") (pin "1") (pinfunction "1_1") (pintype "passive"))
    )
    (net (code "27") (name "I2C1_SDA") (class "Default")
      (node (ref "DISPLAY") (pin "4") (pinfunction "SDA_4") (pintype "bidirectional"))
      (node (ref "IC7") (pin "93") (pinfunction "PB7_93") (pintype "bidirectional"))
      (node (ref "R11") (pin "1") (pinfunction "1_1") (pintype "passive"))
    )
    (net (code "28") (name "LED1") (class "Default")
      (node (ref "IC7") (pin "44") (pinfunction "PE13_44") (pintype "bidirectional"))
      (node (ref "R6") (pin "1") (pinfunction "1_1") (pintype "passive"))
    )
    (net (code "29") (name "LED2") (class "Default")
      (node (ref "IC7") (pin "45") (pinfunction "PE14_45") (pintype "bidirectional"))
      (node (ref "R5") (pin "1") (pinfunction "1_1") (pintype "passive"))
    )
    (net (code "30") (name "LED_SW1") (class "Default")
      (node (ref "IC7") (pin "37") (pinfunction "PB2_37") (pintype "bidirectional"))
      (node (ref "R25") (pin "1") (pinfunction "1_1") (pintype "passive"))
    )
    (net (code "31") (name "LED_SW2") (class "Default")
      (node (ref "IC7") (pin "36") (pinfunction "PB1_36") (pintype "bidirectional"))
      (node (ref "R28") (pin "1") (pinfunction "1_1") (pintype "passive"))
    )
    (net (code "32") (name "LVL") (class "Default")
      (node (ref "IC7") (pin "39") (pinfunction "PE8_39") (pintype "bidirectional"))
      (node (ref "LEVEL") (pin "1") (pinfunction "1_1") (pintype "bidirectional"))
      (node (ref "R7") (pin "2") (pinfunction "2_2") (pintype "passive"))
    )
    (net (code "33") (name "Net-(C8-Pad2)") (class "Default")
      (node (ref "C8") (pin "2") (pinfunction "2_2") (pintype "passive"))
      (node (ref "D2") (pin "A") (pinfunction "A_A") (pintype "passive"))
      (node (ref "USB") (pin "A4") (pinfunction "VBUS_A4") (pintype "power_in"))
      (node (ref "USB") (pin "A9") (pinfunction "VBUS_A9") (pintype "power_in"))
      (node (ref "USB") (pin "B4") (pinfunction "VBUS_B4") (pintype "power_in"))
      (node (ref "USB") (pin "B9") (pinfunction "VBUS_B9") (pintype "power_in"))
    )
    (net (code "34") (name "Net-(CLOCK-CRYSTAL_1)") (class "Default")
      (node (ref "C39") (pin "1") (pinfunction "1_1") (pintype "passive"))
      (node (ref "CLOCK") (pin "1") (pinfunction "CRYSTAL_1_1") (pintype "bidirectional"))
      (node (ref "IC7") (pin "12") (pinfunction "PH0_12") (pintype "bidirectional"))
    )
    (net (code "35") (name "Net-(CLOCK-CRYSTAL_2)") (class "Default")
      (node (ref "C38") (pin "1") (pinfunction "1_1") (pintype "passive"))
      (node (ref "CLOCK") (pin "3") (pinfunction "CRYSTAL_2_3") (pintype "bidirectional"))
      (node (ref "IC7") (pin "13") (pinfunction "PH1_13") (pintype "bidirectional"))
    )
    (net (code "36") (name "Net-(FAULT-PadA)") (class "Default")
      (node (ref "FAULT") (pin "A") (pinfunction "A_A") (pintype "passive"))
      (node (ref "R5") (pin "2") (pinfunction "2_2") (pintype "passive"))
    )
    (net (code "37") (name "Net-(IC1-BST)") (class "Default")
      (node (ref "C16") (pin "2") (pinfunction "2_2") (pintype "passive"))
      (node (ref "IC1") (pin "10") (pinfunction "BST_10") (pintype "bidirectional"))
    )
    (net (code "38") (name "Net-(IC1-LX_1)") (class "Default")
      (node (ref "C16") (pin "1") (pinfunction "1_1") (pintype "passive"))
      (node (ref "IC1") (pin "11") (pinfunction "LX_1_11") (pintype "bidirectional"))
      (node (ref "IC1") (pin "12") (pinfunction "LX_2_12") (pintype "bidirectional"))
      (node (ref "L1") (pin "1") (pinfunction "1_1") (pintype "bidirectional"))
    )
    (net (code "39") (name "Net-(IC1-SS)") (class "Default")
      (node (ref "C14") (pin "1") (pinfunction "1_1") (pintype "passive"))
      (node (ref "IC1") (pin "5") (pinfunction "SS_5") (pintype "bidirectional"))
    )
    (net (code "40") (name "Net-(IC1-VCC)") (class "Default")
      (node (ref "C15") (pin "1") (pinfunction "1_1") (pintype "passive"))
      (node (ref "IC1") (pin "2") (pinfunction "VCC_2") (pintype "bidirectional"))
    )
    (net (code "41") (name "Net-(IC7-VCAP_1)") (class "Default")
      (node (ref "C33") (pin "1") (pinfunction "1_1") (pintype "passive"))
      (node (ref "IC7") (pin "49") (pinfunction "VCAP_1_49") (pintype "bidirectional"))
    )
    (net (code "42") (name "Net-(IC7-VCAP_2)") (class "Default")
      (node (ref "C34") (pin "1") (pinfunction "1_1") (pintype "passive"))
      (node (ref "IC7") (pin "73") (pinfunction "VCAP_2_73") (pintype "bidirectional"))
    )
    (net (code "43") (name "Net-(IC7-VDDA)") (class "Default")
      (node (ref "C35") (pin "1") (pinfunction "1_1") (pintype "passive"))
      (node (ref "C36") (pin "1") (pinfunction "1_1") (pintype "passive"))
      (node (ref "FB") (pin "2") (pinfunction "2_2") (pintype "bidirectional"))
      (node (ref "IC7") (pin "21") (pinfunction "VREF+_21") (pintype "input"))
      (node (ref "IC7") (pin "22") (pinfunction "VDDA_22") (pintype "power_in"))
    )
    (net (code "44") (name "Net-(LS1--)") (class "Default")
      (node (ref "LS1") (pin "3") (pinfunction "-_3") (pintype "bidirectional"))
      (node (ref "Q2") (pin "3") (pinfunction "D_3") (pintype "passive"))
    )
    (net (code "45") (name "Net-(PWR-PadA)") (class "Default")
      (node (ref "PWR") (pin "A") (pinfunction "A_A") (pintype "passive"))
      (node (ref "R16") (pin "2") (pinfunction "2_2") (pintype "passive"))
    )
    (net (code "46") (name "Net-(Q1-D)") (class "Default")
      (node (ref "Q1") (pin "3") (pinfunction "D_3") (pintype "passive"))
      (node (ref "Q3") (pin "1") (pinfunction "G_1") (pintype "bidirectional"))
      (node (ref "R12") (pin "2") (pinfunction "2_2") (pintype "passive"))
    )
    (net (code "47") (name "Net-(Q1-G)") (class "Default")
      (node (ref "Q1") (pin "1") (pinfunction "G_1") (pintype "passive"))
      (node (ref "R13") (pin "2") (pinfunction "2_2") (pintype "passive"))
      (node (ref "R25") (pin "2") (pinfunction "2_2") (pintype "passive"))
    )
    (net (code "48") (name "Net-(Q2-G)") (class "Default")
      (node (ref "Q2") (pin "1") (pinfunction "G_1") (pintype "passive"))
      (node (ref "R40") (pin "2") (pinfunction "2_2") (pintype "passive"))
    )
    (net (code "49") (name "Net-(Q3-S)") (class "Default")
      (node (ref "Q3") (pin "2") (pinfunction "S_2") (pintype "bidirectional"))
      (node (ref "SW/LED") (pin "2") (pinfunction "2_2") (pintype "bidirectional"))
    )
    (net (code "50") (name "Net-(Q4-D)") (class "Default")
      (node (ref "Q4") (pin "3") (pinfunction "D_3") (pintype "passive"))
      (node (ref "Q5") (pin "1") (pinfunction "G_1") (pintype "bidirectional"))
      (node (ref "R26") (pin "2") (pinfunction "2_2") (pintype "passive"))
    )
    (net (code "51") (name "Net-(Q4-G)") (class "Default")
      (node (ref "Q4") (pin "1") (pinfunction "G_1") (pintype "passive"))
      (node (ref "R27") (pin "2") (pinfunction "2_2") (pintype "passive"))
      (node (ref "R28") (pin "2") (pinfunction "2_2") (pintype "passive"))
    )
    (net (code "52") (name "Net-(Q5-S)") (class "Default")
      (node (ref "Q5") (pin "2") (pinfunction "S_2") (pintype "bidirectional"))
      (node (ref "SW/LED") (pin "3") (pinfunction "3_3") (pintype "bidirectional"))
    )
    (net (code "53") (name "Net-(R6-Pad2)") (class "Default")
      (node (ref "R6") (pin "2") (pinfunction "2_2") (pintype "passive"))
      (node (ref "WTR_LOW") (pin "A") (pinfunction "A_A") (pintype "passive"))
    )
    (net (code "54") (name "Net-(R31-Pad2)") (class "Default")
      (node (ref "R31") (pin "2") (pinfunction "2_2") (pintype "passive"))
      (node (ref "STAT") (pin "A") (pinfunction "A_A") (pintype "passive"))
    )
    (net (code "55") (name "Net-(S4-A)") (class "Default")
      (node (ref "C2") (pin "1") (pinfunction "1_1") (pintype "passive"))
      (node (ref "R19") (pin "1") (pinfunction "1_1") (pintype "passive"))
      (node (ref "R20") (pin "1") (pinfunction "1_1") (pintype "passive"))
      (node (ref "S4") (pin "A1") (pinfunction "A_A1") (pintype "bidirectional"))
    )
    (net (code "56") (name "Net-(S4-B)") (class "Default")
      (node (ref "C9") (pin "1") (pinfunction "1_1") (pintype "passive"))
      (node (ref "R18") (pin "1") (pinfunction "1_1") (pintype "passive"))
      (node (ref "R21") (pin "1") (pinfunction "1_1") (pintype "passive"))
      (node (ref "S4") (pin "B1") (pinfunction "B_B1") (pintype "bidirectional"))
    )
    (net (code "57") (name "Net-(USB-CC1)") (class "Default")
      (node (ref "R23") (pin "2") (pinfunction "2_2") (pintype "passive"))
      (node (ref "USB") (pin "A5") (pinfunction "CC1_A5") (pintype "bidirectional"))
    )
    (net (code "58") (name "Net-(USB-CC2)") (class "Default")
      (node (ref "R24") (pin "2") (pinfunction "2_2") (pintype "passive"))
      (node (ref "USB") (pin "B5") (pinfunction "CC2_B5") (pintype "bidirectional"))
    )
    (net (code "59") (name "Net-(USB-DN1)") (class "Default")
      (node (ref "R15") (pin "1") (pinfunction "1_1") (pintype "passive"))
      (node (ref "USB") (pin "A7") (pinfunction "DN1_A7") (pintype "bidirectional"))
      (node (ref "USB") (pin "B7") (pinfunction "DN2_B7") (pintype "bidirectional"))
    )
    (net (code "60") (name "Net-(USB-DP1)") (class "Default")
      (node (ref "R14") (pin "1") (pinfunction "1_1") (pintype "passive"))
      (node (ref "USB") (pin "A6") (pinfunction "DP1_A6") (pintype "bidirectional"))
      (node (ref "USB") (pin "B6") (pinfunction "DP2_B6") (pintype "bidirectional"))
    )
    (net (code "61") (name "P") (class "Default")
      (node (ref "EXT2") (pin "2") (pinfunction "2_2") (pintype "bidirectional"))
      (node (ref "IC7") (pin "15") (pinfunction "PC0_15") (pintype "bidirectional"))
    )
    (net (code "62") (name "RST") (class "Default")
      (node (ref "C5") (pin "1") (pinfunction "1_1") (pintype "passive"))
      (node (ref "IC7") (pin "14") (pinfunction "NRST_14") (pintype "input"))
      (node (ref "R1") (pin "1") (pinfunction "1_1") (pintype "passive"))
      (node (ref "RST") (pin "3") (pinfunction "3_3") (pintype "passive"))
      (node (ref "RST") (pin "4") (pinfunction "4_4") (pintype "passive"))
      (node (ref "SWD") (pin "3") (pinfunction "RST_3") (pintype "bidirectional"))
    )
    (net (code "63") (name "SCLK") (class "Default")
      (node (ref "IC7") (pin "52") (pinfunction "PB13_52") (pintype "bidirectional"))
      (node (ref "TEMPERATURE") (pin "8") (pinfunction "8_8") (pintype "bidirectional"))
    )
    (net (code "64") (name "SDI") (class "Default")
      (node (ref "IC7") (pin "54") (pinfunction "PB15_54") (pintype "bidirectional"))
      (node (ref "TEMPERATURE") (pin "7") (pinfunction "7_7") (pintype "bidirectional"))
    )
    (net (code "65") (name "SDO") (class "Default")
      (node (ref "IC7") (pin "53") (pinfunction "PB14_53") (pintype "bidirectional"))
      (node (ref "TEMPERATURE") (pin "9") (pinfunction "9_9") (pintype "bidirectional"))
    )
    (net (code "66") (name "SERVO") (class "Default")
      (node (ref "IC7") (pin "62") (pinfunction "PD15_62") (pintype "bidirectional"))
      (node (ref "SERVO") (pin "2") (pinfunction "2_2") (pintype "passive"))
    )
    (net (code "67") (name "SPI1_CS") (class "Default")
      (node (ref "IC7") (pin "29") (pinfunction "PA4_29") (pintype "bidirectional"))
      (node (ref "R2") (pin "1") (pinfunction "1_1") (pintype "passive"))
      (node (ref "U5") (pin "1") (pinfunction "~{CS}_1") (pintype "input"))
    )
    (net (code "68") (name "SPI1_MISO") (class "Default")
      (node (ref "IC7") (pin "31") (pinfunction "PA6_31") (pintype "bidirectional"))
      (node (ref "U5") (pin "2") (pinfunction "DO(IO1)_2") (pintype "bidirectional"))
    )
    (net (code "69") (name "SPI1_MOSI") (class "Default")
      (node (ref "IC7") (pin "32") (pinfunction "PA7_32") (pintype "bidirectional"))
      (node (ref "U5") (pin "5") (pinfunction "DI(IO0)_5") (pintype "bidirectional"))
    )
    (net (code "70") (name "SPI1_SCK") (class "Default")
      (node (ref "IC7") (pin "30") (pinfunction "PA5_30") (pintype "bidirectional"))
      (node (ref "U5") (pin "6") (pinfunction "CLK_6") (pintype "input"))
    )
    (net (code "71") (name "STAT") (class "Default")
      (node (ref "IC7") (pin "1") (pinfunction "PE2_1") (pintype "bidirectional"))
      (node (ref "R31") (pin "1") (pinfunction "1_1") (pintype "passive"))
    )
    (net (code "72") (name "STEAM") (class "Default")
      (node (ref "IC7") (pin "38") (pinfunction "PE7_38") (pintype "bidirectional"))
      (node (ref "R9") (pin "2") (pinfunction "2_2") (pintype "passive"))
      (node (ref "STEAM") (pin "1") (pinfunction "1_1") (pintype "bidirectional"))
    )
    (net (code "73") (name "SW2") (class "Default")
      (node (ref "IC7") (pin "35") (pinfunction "PB0_35") (pintype "bidirectional"))
      (node (ref "R8") (pin "2") (pinfunction "2_2") (pintype "passive"))
      (node (ref "SW/LED") (pin "1") (pinfunction "1_1") (pintype "bidirectional"))
    )
    (net (code "74") (name "SWCLK") (class "Default")
      (node (ref "IC7") (pin "76") (pinfunction "PA14_76") (pintype "bidirectional"))
      (node (ref "SWD") (pin "4") (pinfunction "SWCLK_4") (pintype "bidirectional"))
    )
    (net (code "75") (name "SWDIO") (class "Default")
      (node (ref "IC7") (pin "72") (pinfunction "PA13_72") (pintype "bidirectional"))
      (node (ref "SWD") (pin "2") (pinfunction "SWDIO_2") (pintype "bidirectional"))
    )
    (net (code "76") (name "SWO") (class "Default")
      (node (ref "IC7") (pin "89") (pinfunction "PB3_89") (pintype "bidirectional"))
      (node (ref "SWD") (pin "6") (pinfunction "SWO_6") (pintype "bidirectional"))
    )
    (net (code "77") (name "UART3_RX") (class "Default")
      (node (ref "IC7") (pin "56") (pinfunction "PD9_56") (pintype "bidirectional"))
      (node (ref "UART") (pin "3") (pinfunction "3_3") (pintype "passive"))
    )
    (net (code "78") (name "UART3_TX") (class "Default")
      (node (ref "IC7") (pin "55") (pinfunction "PD8_55") (pintype "bidirectional"))
      (node (ref "UART") (pin "2") (pinfunction "2_2") (pintype "passive"))
    )
    (net (code "79") (name "USB_DM") (class "Default")
      (node (ref "IC7") (pin "70") (pinfunction "PA11_70") (pintype "bidirectional"))
      (node (ref "R15") (pin "2") (pinfunction "2_2") (pintype "passive"))
    )
    (net (code "80") (name "USB_DP") (class "Default")
      (node (ref "IC7") (pin "71") (pinfunction "PA12_71") (pintype "bidirectional"))
      (node (ref "R14") (pin "2") (pinfunction "2_2") (pintype "passive"))
    )
    (net (code "81") (name "unconnected-(BOOT0-Pad5)") (class "Default")
      (node (ref "BOOT0") (pin "5") (pinfunction "5_5") (pintype "passive"))
    )
    (net (code "82") (name "unconnected-(BOOT1-Pad5)") (class "Default")
      (node (ref "BOOT1") (pin "5") (pinfunction "5_5") (pintype "passive"))
    )
    (net (code "83") (name "unconnected-(CURRENT-Pad3)") (class "Default")
      (node (ref "CURRENT") (pin "3") (pinfunction "3_3") (pintype "bidirectional"))
    )
    (net (code "84") (name "unconnected-(EXT1-Pad3)") (class "Default")
      (node (ref "EXT1") (pin "3") (pinfunction "3_3") (pintype "bidirectional"))
    )
    (net (code "85") (name "unconnected-(EXT1-Pad8)") (class "Default")
      (node (ref "EXT1") (pin "8") (pinfunction "8_8") (pintype "bidirectional"))
    )
    (net (code "86") (name "unconnected-(EXT1-Pad9)") (class "Default")
      (node (ref "EXT1") (pin "9") (pinfunction "9_9") (pintype "bidirectional"))
    )
    (net (code "87") (name "unconnected-(IC1-RT-Pad7)") (class "Default")
      (node (ref "IC1") (pin "7") (pinfunction "RT_7") (pintype "bidirectional"))
    )
    (net (code "88") (name "unconnected-(IC1-~{RESET}-Pad8)") (class "Default")
      (node (ref "IC1") (pin "8") (pinfunction "~{RESET}_8") (pintype "bidirectional"))
    )
    (net (code "89") (name "unconnected-(IC2-BYP-Pad4)") (class "Default")
      (node (ref "IC2") (pin "4") (pinfunction "BYP_4") (pintype "output"))
    )
    (net (code "90") (name "unconnected-(IC7-PA0-Pad23)") (class "Default")
      (node (ref "IC7") (pin "23") (pinfunction "PA0_23") (pintype "bidirectional"))
    )
    (net (code "91") (name "unconnected-(IC7-PA1-Pad24)") (class "Default")
      (node (ref "IC7") (pin "24") (pinfunction "PA1_24") (pintype "bidirectional"))
    )
    (net (code "92") (name "unconnected-(IC7-PA2-Pad25)") (class "Default")
      (node (ref "IC7") (pin "25") (pinfunction "PA2_25") (pintype "bidirectional"))
    )
    (net (code "93") (name "unconnected-(IC7-PA9-Pad68)") (class "Default")
      (node (ref "IC7") (pin "68") (pinfunction "PA9_68") (pintype "bidirectional"))
    )
    (net (code "94") (name "unconnected-(IC7-PA10-Pad69)") (class "Default")
      (node (ref "IC7") (pin "69") (pinfunction "PA10_69") (pintype "bidirectional"))
    )
    (net (code "95") (name "unconnected-(IC7-PB4-Pad90)") (class "Default")
      (node (ref "IC7") (pin "90") (pinfunction "PB4_90") (pintype "bidirectional"))
    )
    (net (code "96") (name "unconnected-(IC7-PB5-Pad91)") (class "Default")
      (node (ref "IC7") (pin "91") (pinfunction "PB5_91") (pintype "bidirectional"))
    )
    (net (code "97") (name "unconnected-(IC7-PB8-Pad95)") (class "Default")
      (node (ref "IC7") (pin "95") (pinfunction "PB8_95") (pintype "bidirectional"))
    )
    (net (code "98") (name "unconnected-(IC7-PB9-Pad96)") (class "Default")
      (node (ref "IC7") (pin "96") (pinfunction "PB9_96") (pintype "bidirectional"))
    )
    (net (code "99") (name "unconnected-(IC7-PB10-Pad47)") (class "Default")
      (node (ref "IC7") (pin "47") (pinfunction "PB10_47") (pintype "bidirectional"))
    )
    (net (code "100") (name "unconnected-(IC7-PB11-Pad48)") (class "Default")
      (node (ref "IC7") (pin "48") (pinfunction "PB11_48") (pintype "bidirectional"))
    )
    (net (code "101") (name "unconnected-(IC7-PB12-Pad51)") (class "Default")
      (node (ref "IC7") (pin "51") (pinfunction "PB12_51") (pintype "bidirectional"))
    )
    (net (code "102") (name "unconnected-(IC7-PC2-Pad17)") (class "Default")
      (node (ref "IC7") (pin "17") (pinfunction "PC2_17") (pintype "bidirectional"))
    )
    (net (code "103") (name "unconnected-(IC7-PC3-Pad18)") (class "Default")
      (node (ref "IC7") (pin "18") (pinfunction "PC3_18") (pintype "bidirectional"))
    )
    (net (code "104") (name "unconnected-(IC7-PC4-Pad33)") (class "Default")
      (node (ref "IC7") (pin "33") (pinfunction "PC4_33") (pintype "bidirectional"))
    )
    (net (code "105") (name "unconnected-(IC7-PC5-Pad34)") (class "Default")
      (node (ref "IC7") (pin "34") (pinfunction "PC5_34") (pintype "bidirectional"))
    )
    (net (code "106") (name "unconnected-(IC7-PC13-Pad7)") (class "Default")
      (node (ref "IC7") (pin "7") (pinfunction "PC13_7") (pintype "bidirectional"))
    )
    (net (code "107") (name "unconnected-(IC7-PC14-Pad8)") (class "Default")
      (node (ref "IC7") (pin "8") (pinfunction "PC14_8") (pintype "bidirectional"))
    )
    (net (code "108") (name "unconnected-(IC7-PC15-Pad9)") (class "Default")
      (node (ref "IC7") (pin "9") (pinfunction "PC15_9") (pintype "bidirectional"))
    )
    (net (code "109") (name "unconnected-(IC7-PD0-Pad81)") (class "Default")
      (node (ref "IC7") (pin "81") (pinfunction "PD0_81") (pintype "bidirectional"))
    )
    (net (code "110") (name "unconnected-(IC7-PD1-Pad82)") (class "Default")
      (node (ref "IC7") (pin "82") (pinfunction "PD1_82") (pintype "bidirectional"))
    )
    (net (code "111") (name "unconnected-(IC7-PD2-Pad83)") (class "Default")
      (node (ref "IC7") (pin "83") (pinfunction "PD2_83") (pintype "bidirectional"))
    )
    (net (code "112") (name "unconnected-(IC7-PD3-Pad84)") (class "Default")
      (node (ref "IC7") (pin "84") (pinfunction "PD3_84") (pintype "bidirectional"))
    )
    (net (code "113") (name "unconnected-(IC7-PD4-Pad85)") (class "Default")
      (node (ref "IC7") (pin "85") (pinfunction "PD4_85") (pintype "bidirectional"))
    )
    (net (code "114") (name "unconnected-(IC7-PD5-Pad86)") (class "Default")
      (node (ref "IC7") (pin "86") (pinfunction "PD5_86") (pintype "bidirectional"))
    )
    (net (code "115") (name "unconnected-(IC7-PD6-Pad87)") (class "Default")
      (node (ref "IC7") (pin "87") (pinfunction "PD6_87") (pintype "bidirectional"))
    )
    (net (code "116") (name "unconnected-(IC7-PD7-Pad88)") (class "Default")
      (node (ref "IC7") (pin "88") (pinfunction "PD7_88") (pintype "bidirectional"))
    )
    (net (code "117") (name "unconnected-(IC7-PE0-Pad97)") (class "Default")
      (node (ref "IC7") (pin "97") (pinfunction "PE0_97") (pintype "bidirectional"))
    )
    (net (code "118") (name "unconnected-(IC7-PE1-Pad98)") (class "Default")
      (node (ref "IC7") (pin "98") (pinfunction "PE1_98") (pintype "bidirectional"))
    )
    (net (code "119") (name "unconnected-(IC7-PE3-Pad2)") (class "Default")
      (node (ref "IC7") (pin "2") (pinfunction "PE3_2") (pintype "bidirectional"))
    )
    (net (code "120") (name "unconnected-(IC7-PE4-Pad3)") (class "Default")
      (node (ref "IC7") (pin "3") (pinfunction "PE4_3") (pintype "bidirectional"))
    )
    (net (code "121") (name "unconnected-(IC7-PE5-Pad4)") (class "Default")
      (node (ref "IC7") (pin "4") (pinfunction "PE5_4") (pintype "bidirectional"))
    )
    (net (code "122") (name "unconnected-(IC7-PE6-Pad5)") (class "Default")
      (node (ref "IC7") (pin "5") (pinfunction "PE6_5") (pintype "bidirectional"))
    )
    (net (code "123") (name "unconnected-(IC7-PE12-Pad43)") (class "Default")
      (node (ref "IC7") (pin "43") (pinfunction "PE12_43") (pintype "bidirectional"))
    )
    (net (code "124") (name "unconnected-(IC7-PE15-Pad46)") (class "Default")
      (node (ref "IC7") (pin "46") (pinfunction "PE15_46") (pintype "bidirectional"))
    )
    (net (code "125") (name "unconnected-(LS1-NC_1-Pad1)") (class "Default")
      (node (ref "LS1") (pin "1") (pinfunction "NC_1_1") (pintype "bidirectional"))
    )
    (net (code "126") (name "unconnected-(LS1-NC_2-Pad4)") (class "Default")
      (node (ref "LS1") (pin "4") (pinfunction "NC_2_4") (pintype "bidirectional"))
    )
    (net (code "127") (name "unconnected-(RST-Pad5)") (class "Default")
      (node (ref "RST") (pin "5") (pinfunction "5_5") (pintype "passive"))
    )
    (net (code "128") (name "unconnected-(S4-PadMH1)") (class "Default")
      (node (ref "S4") (pin "MH1") (pinfunction "MH1_MH1") (pintype "bidirectional"))
    )
    (net (code "129") (name "unconnected-(S4-PadMH2)") (class "Default")
      (node (ref "S4") (pin "MH2") (pinfunction "MH2_MH2") (pintype "bidirectional"))
    )
    (net (code "130") (name "unconnected-(USB-SBU1-PadA8)") (class "Default")
      (node (ref "USB") (pin "A8") (pinfunction "SBU1_A8") (pintype "bidirectional"))
    )
    (net (code "131") (name "unconnected-(USB-SBU2-PadB8)") (class "Default")
      (node (ref "USB") (pin "B8") (pinfunction "SBU2_B8") (pintype "bidirectional"))
    )
  )
)
